# 7_Analogue.net
KiCad netlist of a schematic drawn in Altium Designer
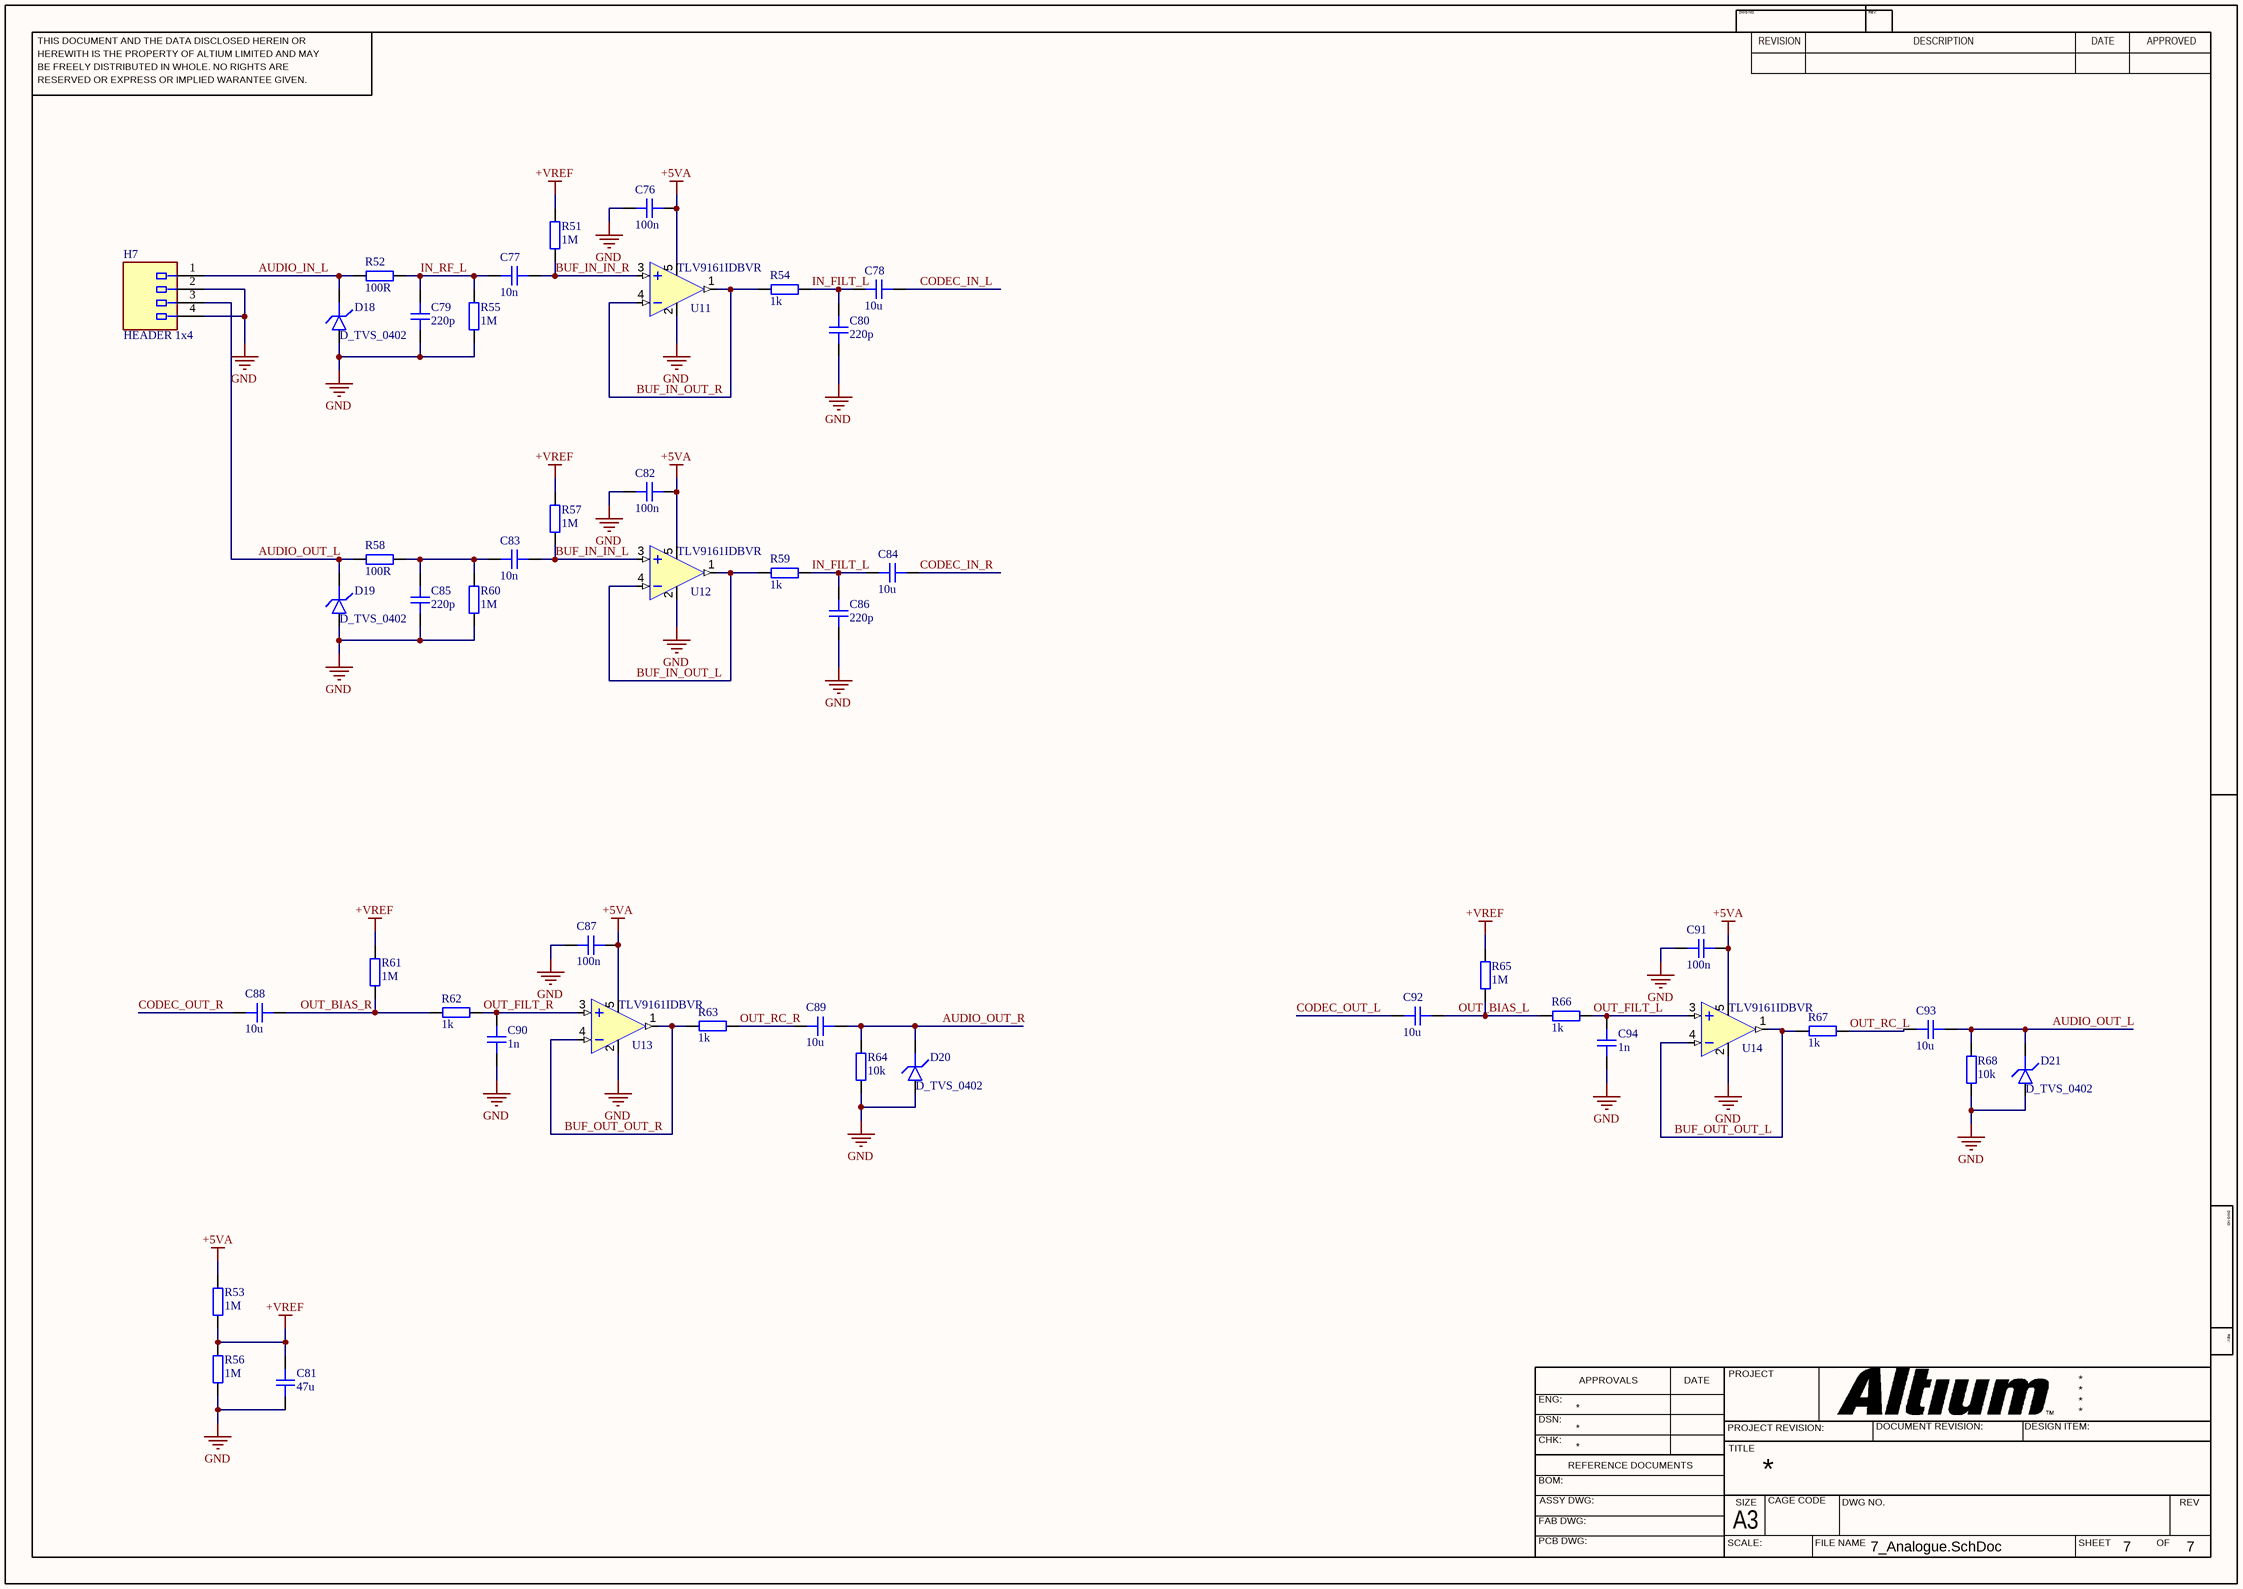
[diagram p0: 7_Analogue.SchDoc]

(export (version "E")
  (design (tool "Eeschema 10.0.6"))
  (components
    (comp (ref "C76")
      (value "100n")
      (footprint "CAP_0402")
      (description "Capacitor SMD 0402")
      (libsource (lib "Schematic-Lib-PhilsLab") (part "CAP_0402"))
    )
    (comp (ref "C77")
      (value "10n")
      (footprint "CAP_0402")
      (description "Capacitor SMD 0402")
      (libsource (lib "Schematic-Lib-PhilsLab") (part "CAP_0402"))
    )
    (comp (ref "C78")
      (value "10u")
      (footprint "CAP_0402")
      (description "Capacitor SMD 0402")
      (libsource (lib "Schematic-Lib-PhilsLab") (part "CAP_0402"))
    )
    (comp (ref "C79")
      (value "220p")
      (footprint "CAP_0402")
      (description "Capacitor SMD 0402")
      (libsource (lib "Schematic-Lib-PhilsLab") (part "CAP_0402"))
    )
    (comp (ref "C80")
      (value "220p")
      (footprint "CAP_0402")
      (description "Capacitor SMD 0402")
      (libsource (lib "Schematic-Lib-PhilsLab") (part "CAP_0402"))
    )
    (comp (ref "C81")
      (value "47u")
      (footprint "CAP_0402")
      (description "Capacitor SMD 0402")
      (libsource (lib "Schematic-Lib-PhilsLab") (part "CAP_0402"))
    )
    (comp (ref "C82")
      (value "100n")
      (footprint "CAP_0402")
      (description "Capacitor SMD 0402")
      (libsource (lib "Schematic-Lib-PhilsLab") (part "CAP_0402"))
    )
    (comp (ref "C83")
      (value "10n")
      (footprint "CAP_0402")
      (description "Capacitor SMD 0402")
      (libsource (lib "Schematic-Lib-PhilsLab") (part "CAP_0402"))
    )
    (comp (ref "C84")
      (value "10u")
      (footprint "CAP_0402")
      (description "Capacitor SMD 0402")
      (libsource (lib "Schematic-Lib-PhilsLab") (part "CAP_0402"))
    )
    (comp (ref "C85")
      (value "220p")
      (footprint "CAP_0402")
      (description "Capacitor SMD 0402")
      (libsource (lib "Schematic-Lib-PhilsLab") (part "CAP_0402"))
    )
    (comp (ref "C86")
      (value "220p")
      (footprint "CAP_0402")
      (description "Capacitor SMD 0402")
      (libsource (lib "Schematic-Lib-PhilsLab") (part "CAP_0402"))
    )
    (comp (ref "C87")
      (value "100n")
      (footprint "CAP_0402")
      (description "Capacitor SMD 0402")
      (libsource (lib "Schematic-Lib-PhilsLab") (part "CAP_0402"))
    )
    (comp (ref "C88")
      (value "10u")
      (footprint "CAP_0402")
      (description "Capacitor SMD 0402")
      (libsource (lib "Schematic-Lib-PhilsLab") (part "CAP_0402"))
    )
    (comp (ref "C89")
      (value "10u")
      (footprint "CAP_0402")
      (description "Capacitor SMD 0402")
      (libsource (lib "Schematic-Lib-PhilsLab") (part "CAP_0402"))
    )
    (comp (ref "C90")
      (value "1n")
      (footprint "CAP_0402")
      (description "Capacitor SMD 0402")
      (libsource (lib "Schematic-Lib-PhilsLab") (part "CAP_0402"))
    )
    (comp (ref "C91")
      (value "100n")
      (footprint "CAP_0402")
      (description "Capacitor SMD 0402")
      (libsource (lib "Schematic-Lib-PhilsLab") (part "CAP_0402"))
    )
    (comp (ref "C92")
      (value "10u")
      (footprint "CAP_0402")
      (description "Capacitor SMD 0402")
      (libsource (lib "Schematic-Lib-PhilsLab") (part "CAP_0402"))
    )
    (comp (ref "C93")
      (value "10u")
      (footprint "CAP_0402")
      (description "Capacitor SMD 0402")
      (libsource (lib "Schematic-Lib-PhilsLab") (part "CAP_0402"))
    )
    (comp (ref "C94")
      (value "1n")
      (footprint "CAP_0402")
      (description "Capacitor SMD 0402")
      (libsource (lib "Schematic-Lib-PhilsLab") (part "CAP_0402"))
    )
    (comp (ref "D18")
      (value "D_TVS_0402")
      (footprint "D_0402")
      (description "Diode TVS / ESD 0402")
      (libsource (lib "Schematic-Lib-PhilsLab") (part "D_TVS_0402"))
    )
    (comp (ref "D19")
      (value "D_TVS_0402")
      (footprint "D_0402")
      (description "Diode TVS / ESD 0402")
      (libsource (lib "Schematic-Lib-PhilsLab") (part "D_TVS_0402"))
    )
    (comp (ref "D20")
      (value "D_TVS_0402")
      (footprint "D_0402")
      (description "Diode TVS / ESD 0402")
      (libsource (lib "Schematic-Lib-PhilsLab") (part "D_TVS_0402"))
    )
    (comp (ref "D21")
      (value "D_TVS_0402")
      (footprint "D_0402")
      (description "Diode TVS / ESD 0402")
      (libsource (lib "Schematic-Lib-PhilsLab") (part "D_TVS_0402"))
    )
    (comp (ref "H7")
      (value "HEADER 1x4")
      (footprint "053048-0410")
      (libsource (lib "SCHLib") (part "053048-0410"))
    )
    (comp (ref "R51")
      (value "1M")
      (footprint "RES_0402")
      (description "Resistor SMD 0402")
      (libsource (lib "Schematic-Lib-PhilsLab") (part "RES_0402"))
    )
    (comp (ref "R52")
      (value "100R")
      (footprint "RES_0402")
      (description "Resistor SMD 0402")
      (libsource (lib "Schematic-Lib-PhilsLab") (part "RES_0402"))
    )
    (comp (ref "R53")
      (value "1M")
      (footprint "RES_0402")
      (description "Resistor SMD 0402")
      (libsource (lib "Schematic-Lib-PhilsLab") (part "RES_0402"))
    )
    (comp (ref "R54")
      (value "1k")
      (footprint "RES_0402")
      (description "Resistor SMD 0402")
      (libsource (lib "Schematic-Lib-PhilsLab") (part "RES_0402"))
    )
    (comp (ref "R55")
      (value "1M")
      (footprint "RES_0402")
      (description "Resistor SMD 0402")
      (libsource (lib "Schematic-Lib-PhilsLab") (part "RES_0402"))
    )
    (comp (ref "R56")
      (value "1M")
      (footprint "RES_0402")
      (description "Resistor SMD 0402")
      (libsource (lib "Schematic-Lib-PhilsLab") (part "RES_0402"))
    )
    (comp (ref "R57")
      (value "1M")
      (footprint "RES_0402")
      (description "Resistor SMD 0402")
      (libsource (lib "Schematic-Lib-PhilsLab") (part "RES_0402"))
    )
    (comp (ref "R58")
      (value "100R")
      (footprint "RES_0402")
      (description "Resistor SMD 0402")
      (libsource (lib "Schematic-Lib-PhilsLab") (part "RES_0402"))
    )
    (comp (ref "R59")
      (value "1k")
      (footprint "RES_0402")
      (description "Resistor SMD 0402")
      (libsource (lib "Schematic-Lib-PhilsLab") (part "RES_0402"))
    )
    (comp (ref "R60")
      (value "1M")
      (footprint "RES_0402")
      (description "Resistor SMD 0402")
      (libsource (lib "Schematic-Lib-PhilsLab") (part "RES_0402"))
    )
    (comp (ref "R61")
      (value "1M")
      (footprint "RES_0402")
      (description "Resistor SMD 0402")
      (libsource (lib "Schematic-Lib-PhilsLab") (part "RES_0402"))
    )
    (comp (ref "R62")
      (value "1k")
      (footprint "RES_0402")
      (description "Resistor SMD 0402")
      (libsource (lib "Schematic-Lib-PhilsLab") (part "RES_0402"))
    )
    (comp (ref "R63")
      (value "1k")
      (footprint "RES_0402")
      (description "Resistor SMD 0402")
      (libsource (lib "Schematic-Lib-PhilsLab") (part "RES_0402"))
    )
    (comp (ref "R64")
      (value "10k")
      (footprint "RES_0402")
      (description "Resistor SMD 0402")
      (libsource (lib "Schematic-Lib-PhilsLab") (part "RES_0402"))
    )
    (comp (ref "R65")
      (value "1M")
      (footprint "RES_0402")
      (description "Resistor SMD 0402")
      (libsource (lib "Schematic-Lib-PhilsLab") (part "RES_0402"))
    )
    (comp (ref "R66")
      (value "1k")
      (footprint "RES_0402")
      (description "Resistor SMD 0402")
      (libsource (lib "Schematic-Lib-PhilsLab") (part "RES_0402"))
    )
    (comp (ref "R67")
      (value "1k")
      (footprint "RES_0402")
      (description "Resistor SMD 0402")
      (libsource (lib "Schematic-Lib-PhilsLab") (part "RES_0402"))
    )
    (comp (ref "R68")
      (value "10k")
      (footprint "RES_0402")
      (description "Resistor SMD 0402")
      (libsource (lib "Schematic-Lib-PhilsLab") (part "RES_0402"))
    )
    (comp (ref "U11")
      (value "TLV9161IDBVR")
      (footprint "SOT-23-5")
      (description "TLV916x 16-V, 11-MHz, Rail-to-Rail Input/Output, Low Offset Voltage, Low Noise Op Amp SOT-23-5")
      (fields (field (name "MANUFACTURER") "Texas Instruments"))
      (libsource (lib "Schematic-Lib-PhilsLab") (part "TLV9161IDBVR"))
    )
    (comp (ref "U12")
      (value "TLV9161IDBVR")
      (footprint "SOT-23-5")
      (description "TLV916x 16-V, 11-MHz, Rail-to-Rail Input/Output, Low Offset Voltage, Low Noise Op Amp SOT-23-5")
      (fields (field (name "MANUFACTURER") "Texas Instruments"))
      (libsource (lib "Schematic-Lib-PhilsLab") (part "TLV9161IDBVR"))
    )
    (comp (ref "U13")
      (value "TLV9161IDBVR")
      (footprint "SOT-23-5")
      (description "TLV916x 16-V, 11-MHz, Rail-to-Rail Input/Output, Low Offset Voltage, Low Noise Op Amp SOT-23-5")
      (fields (field (name "MANUFACTURER") "Texas Instruments"))
      (libsource (lib "Schematic-Lib-PhilsLab") (part "TLV9161IDBVR"))
    )
    (comp (ref "U14")
      (value "TLV9161IDBVR")
      (footprint "SOT-23-5")
      (description "TLV916x 16-V, 11-MHz, Rail-to-Rail Input/Output, Low Offset Voltage, Low Noise Op Amp SOT-23-5")
      (fields (field (name "MANUFACTURER") "Texas Instruments"))
      (libsource (lib "Schematic-Lib-PhilsLab") (part "TLV9161IDBVR"))
    )
  )
  (nets
    (net (code "1") (name "+5VA") (class "Default")
      (node (ref "C76") (pin "1") (pinfunction "1_1") (pintype "passive"))
      (node (ref "C82") (pin "1") (pinfunction "1_1") (pintype "passive"))
      (node (ref "C87") (pin "1") (pinfunction "1_1") (pintype "passive"))
      (node (ref "C91") (pin "1") (pinfunction "1_1") (pintype "passive"))
      (node (ref "R53") (pin "2") (pinfunction "2_2") (pintype "passive"))
      (node (ref "U11") (pin "5") (pinfunction "V+_5") (pintype "passive"))
      (node (ref "U12") (pin "5") (pinfunction "V+_5") (pintype "passive"))
      (node (ref "U13") (pin "5") (pinfunction "V+_5") (pintype "passive"))
      (node (ref "U14") (pin "5") (pinfunction "V+_5") (pintype "passive"))
    )
    (net (code "2") (name "+VREF") (class "Default")
      (node (ref "C81") (pin "1") (pinfunction "1_1") (pintype "passive"))
      (node (ref "R51") (pin "2") (pinfunction "2_2") (pintype "passive"))
      (node (ref "R53") (pin "1") (pinfunction "1_1") (pintype "passive"))
      (node (ref "R56") (pin "2") (pinfunction "2_2") (pintype "passive"))
      (node (ref "R57") (pin "2") (pinfunction "2_2") (pintype "passive"))
      (node (ref "R61") (pin "2") (pinfunction "2_2") (pintype "passive"))
      (node (ref "R65") (pin "2") (pinfunction "2_2") (pintype "passive"))
    )
    (net (code "3") (name "/AUDIO_IN_L") (class "Default")
      (node (ref "D18") (pin "K") (pinfunction "K_K") (pintype "passive"))
      (node (ref "H7") (pin "1") (pinfunction "1_1") (pintype "passive"))
      (node (ref "R52") (pin "1") (pinfunction "1_1") (pintype "passive"))
    )
    (net (code "4") (name "/AUDIO_OUT_L") (class "Default")
      (node (ref "C93") (pin "1") (pinfunction "1_1") (pintype "passive"))
      (node (ref "D19") (pin "K") (pinfunction "K_K") (pintype "passive"))
      (node (ref "D21") (pin "K") (pinfunction "K_K") (pintype "passive"))
      (node (ref "H7") (pin "3") (pinfunction "3_3") (pintype "passive"))
      (node (ref "R58") (pin "1") (pinfunction "1_1") (pintype "passive"))
      (node (ref "R68") (pin "1") (pinfunction "1_1") (pintype "passive"))
    )
    (net (code "5") (name "/AUDIO_OUT_R") (class "Default")
      (node (ref "C89") (pin "1") (pinfunction "1_1") (pintype "passive"))
      (node (ref "D20") (pin "K") (pinfunction "K_K") (pintype "passive"))
      (node (ref "R64") (pin "1") (pinfunction "1_1") (pintype "passive"))
    )
    (net (code "6") (name "/BUF_IN_IN_L") (class "Default")
      (node (ref "C83") (pin "1") (pinfunction "1_1") (pintype "passive"))
      (node (ref "R57") (pin "1") (pinfunction "1_1") (pintype "passive"))
      (node (ref "U12") (pin "3") (pinfunction "IN+_3") (pintype "input"))
    )
    (net (code "7") (name "/BUF_IN_IN_R") (class "Default")
      (node (ref "C77") (pin "1") (pinfunction "1_1") (pintype "passive"))
      (node (ref "R51") (pin "1") (pinfunction "1_1") (pintype "passive"))
      (node (ref "U11") (pin "3") (pinfunction "IN+_3") (pintype "input"))
    )
    (net (code "8") (name "/BUF_IN_OUT_L") (class "Default")
      (node (ref "R59") (pin "2") (pinfunction "2_2") (pintype "passive"))
      (node (ref "U12") (pin "1") (pinfunction "OUT_1") (pintype "output"))
      (node (ref "U12") (pin "4") (pinfunction "IN-_4") (pintype "input"))
    )
    (net (code "9") (name "/BUF_IN_OUT_R") (class "Default")
      (node (ref "R54") (pin "2") (pinfunction "2_2") (pintype "passive"))
      (node (ref "U11") (pin "1") (pinfunction "OUT_1") (pintype "output"))
      (node (ref "U11") (pin "4") (pinfunction "IN-_4") (pintype "input"))
    )
    (net (code "10") (name "/BUF_OUT_OUT_L") (class "Default")
      (node (ref "R67") (pin "2") (pinfunction "2_2") (pintype "passive"))
      (node (ref "U14") (pin "1") (pinfunction "OUT_1") (pintype "output"))
      (node (ref "U14") (pin "4") (pinfunction "IN-_4") (pintype "input"))
    )
    (net (code "11") (name "/BUF_OUT_OUT_R") (class "Default")
      (node (ref "R63") (pin "2") (pinfunction "2_2") (pintype "passive"))
      (node (ref "U13") (pin "1") (pinfunction "OUT_1") (pintype "output"))
      (node (ref "U13") (pin "4") (pinfunction "IN-_4") (pintype "input"))
    )
    (net (code "12") (name "/CODEC_IN_L") (class "Default")
      (node (ref "C78") (pin "1") (pinfunction "1_1") (pintype "passive"))
    )
    (net (code "13") (name "/CODEC_IN_R") (class "Default")
      (node (ref "C84") (pin "1") (pinfunction "1_1") (pintype "passive"))
    )
    (net (code "14") (name "/CODEC_OUT_L") (class "Default")
      (node (ref "C92") (pin "2") (pinfunction "2_2") (pintype "passive"))
    )
    (net (code "15") (name "/CODEC_OUT_R") (class "Default")
      (node (ref "C88") (pin "2") (pinfunction "2_2") (pintype "passive"))
    )
    (net (code "16") (name "/IN_FILT_L") (class "Default")
      (node (ref "C78") (pin "2") (pinfunction "2_2") (pintype "passive"))
      (node (ref "C80") (pin "1") (pinfunction "1_1") (pintype "passive"))
      (node (ref "C84") (pin "2") (pinfunction "2_2") (pintype "passive"))
      (node (ref "C86") (pin "1") (pinfunction "1_1") (pintype "passive"))
      (node (ref "R54") (pin "1") (pinfunction "1_1") (pintype "passive"))
      (node (ref "R59") (pin "1") (pinfunction "1_1") (pintype "passive"))
    )
    (net (code "17") (name "/IN_RF_L") (class "Default")
      (node (ref "C77") (pin "2") (pinfunction "2_2") (pintype "passive"))
      (node (ref "C79") (pin "2") (pinfunction "2_2") (pintype "passive"))
      (node (ref "R52") (pin "2") (pinfunction "2_2") (pintype "passive"))
      (node (ref "R55") (pin "2") (pinfunction "2_2") (pintype "passive"))
    )
    (net (code "18") (name "/OUT_BIAS_L") (class "Default")
      (node (ref "C92") (pin "1") (pinfunction "1_1") (pintype "passive"))
      (node (ref "R65") (pin "1") (pinfunction "1_1") (pintype "passive"))
      (node (ref "R66") (pin "2") (pinfunction "2_2") (pintype "passive"))
    )
    (net (code "19") (name "/OUT_BIAS_R") (class "Default")
      (node (ref "C88") (pin "1") (pinfunction "1_1") (pintype "passive"))
      (node (ref "R61") (pin "1") (pinfunction "1_1") (pintype "passive"))
      (node (ref "R62") (pin "2") (pinfunction "2_2") (pintype "passive"))
    )
    (net (code "20") (name "/OUT_FILT_L") (class "Default")
      (node (ref "C94") (pin "1") (pinfunction "1_1") (pintype "passive"))
      (node (ref "R66") (pin "1") (pinfunction "1_1") (pintype "passive"))
      (node (ref "U14") (pin "3") (pinfunction "IN+_3") (pintype "input"))
    )
    (net (code "21") (name "/OUT_FILT_R") (class "Default")
      (node (ref "C90") (pin "1") (pinfunction "1_1") (pintype "passive"))
      (node (ref "R62") (pin "1") (pinfunction "1_1") (pintype "passive"))
      (node (ref "U13") (pin "3") (pinfunction "IN+_3") (pintype "input"))
    )
    (net (code "22") (name "/OUT_RC_L") (class "Default")
      (node (ref "C93") (pin "2") (pinfunction "2_2") (pintype "passive"))
      (node (ref "R67") (pin "1") (pinfunction "1_1") (pintype "passive"))
    )
    (net (code "23") (name "/OUT_RC_R") (class "Default")
      (node (ref "C89") (pin "2") (pinfunction "2_2") (pintype "passive"))
      (node (ref "R63") (pin "1") (pinfunction "1_1") (pintype "passive"))
    )
    (net (code "24") (name "GND") (class "Default")
      (node (ref "C76") (pin "2") (pinfunction "2_2") (pintype "passive"))
      (node (ref "C79") (pin "1") (pinfunction "1_1") (pintype "passive"))
      (node (ref "C80") (pin "2") (pinfunction "2_2") (pintype "passive"))
      (node (ref "C81") (pin "2") (pinfunction "2_2") (pintype "passive"))
      (node (ref "C82") (pin "2") (pinfunction "2_2") (pintype "passive"))
      (node (ref "C85") (pin "1") (pinfunction "1_1") (pintype "passive"))
      (node (ref "C86") (pin "2") (pinfunction "2_2") (pintype "passive"))
      (node (ref "C87") (pin "2") (pinfunction "2_2") (pintype "passive"))
      (node (ref "C90") (pin "2") (pinfunction "2_2") (pintype "passive"))
      (node (ref "C91") (pin "2") (pinfunction "2_2") (pintype "passive"))
      (node (ref "C94") (pin "2") (pinfunction "2_2") (pintype "passive"))
      (node (ref "D18") (pin "A") (pinfunction "A_A") (pintype "passive"))
      (node (ref "D19") (pin "A") (pinfunction "A_A") (pintype "passive"))
      (node (ref "D20") (pin "A") (pinfunction "A_A") (pintype "passive"))
      (node (ref "D21") (pin "A") (pinfunction "A_A") (pintype "passive"))
      (node (ref "H7") (pin "2") (pinfunction "2_2") (pintype "passive"))
      (node (ref "H7") (pin "4") (pinfunction "4_4") (pintype "passive"))
      (node (ref "R55") (pin "1") (pinfunction "1_1") (pintype "passive"))
      (node (ref "R56") (pin "1") (pinfunction "1_1") (pintype "passive"))
      (node (ref "R60") (pin "1") (pinfunction "1_1") (pintype "passive"))
      (node (ref "R64") (pin "2") (pinfunction "2_2") (pintype "passive"))
      (node (ref "R68") (pin "2") (pinfunction "2_2") (pintype "passive"))
      (node (ref "U11") (pin "2") (pinfunction "V-_2") (pintype "passive"))
      (node (ref "U12") (pin "2") (pinfunction "V-_2") (pintype "passive"))
      (node (ref "U13") (pin "2") (pinfunction "V-_2") (pintype "passive"))
      (node (ref "U14") (pin "2") (pinfunction "V-_2") (pintype "passive"))
    )
    (net (code "25") (name "Net-(C83-Pad2)") (class "Default")
      (node (ref "C83") (pin "2") (pinfunction "2_2") (pintype "passive"))
      (node (ref "C85") (pin "2") (pinfunction "2_2") (pintype "passive"))
      (node (ref "R58") (pin "2") (pinfunction "2_2") (pintype "passive"))
      (node (ref "R60") (pin "2") (pinfunction "2_2") (pintype "passive"))
    )
  )
)
